# LPC824DIP.net
KiCad netlist of a schematic drawn in EAGLE
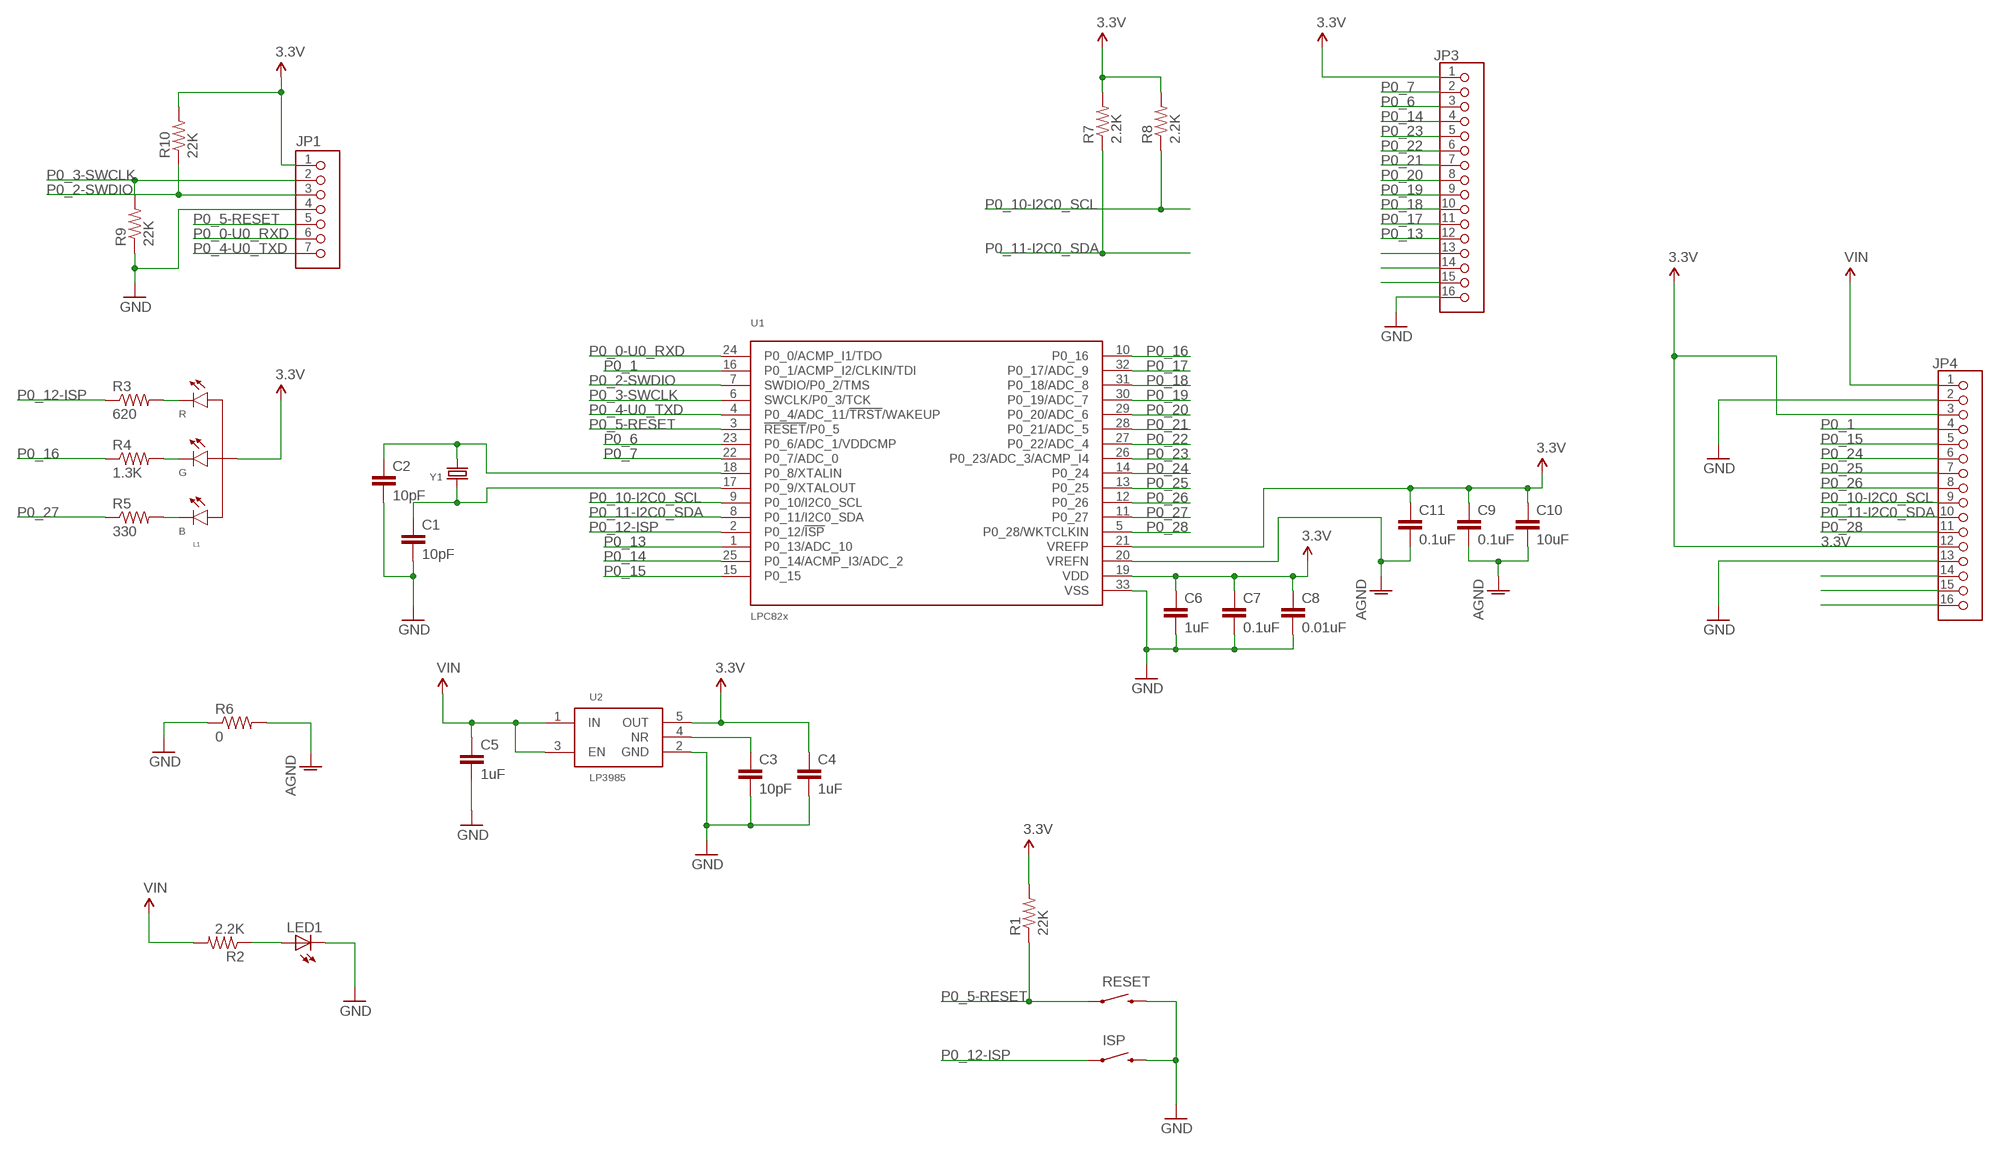
[diagram p0: schematic, sheet 1]

(export (version "E")
  (design (tool "Eeschema 10.0.6"))
  (components
    (comp (ref "C1")
      (value "10pF")
      (footprint "eagle-import:C0402")
      (libsource (lib "eagle-import") (part "C0402"))
    )
    (comp (ref "C2")
      (value "10pF")
      (footprint "eagle-import:C0402")
      (libsource (lib "eagle-import") (part "C0402"))
    )
    (comp (ref "C3")
      (value "10pF")
      (footprint "eagle-import:C0402")
      (libsource (lib "eagle-import") (part "C0402"))
    )
    (comp (ref "C4")
      (value "1uF")
      (footprint "eagle-import:C0402")
      (libsource (lib "eagle-import") (part "C0402"))
    )
    (comp (ref "C5")
      (value "1uF")
      (footprint "eagle-import:C0402")
      (libsource (lib "eagle-import") (part "C0402"))
    )
    (comp (ref "C6")
      (value "1uF")
      (footprint "eagle-import:C0402")
      (libsource (lib "eagle-import") (part "C0402"))
    )
    (comp (ref "C7")
      (value "0.1uF")
      (footprint "eagle-import:C0402")
      (libsource (lib "eagle-import") (part "C0402"))
    )
    (comp (ref "C8")
      (value "0.01uF")
      (footprint "eagle-import:C0402")
      (libsource (lib "eagle-import") (part "C0402"))
    )
    (comp (ref "C9")
      (value "0.1uF")
      (footprint "eagle-import:C0402")
      (libsource (lib "eagle-import") (part "C0402"))
    )
    (comp (ref "C10")
      (value "10uF")
      (footprint "eagle-import:C0402")
      (libsource (lib "eagle-import") (part "C0402"))
    )
    (comp (ref "C11")
      (value "0.1uF")
      (footprint "eagle-import:C0402")
      (libsource (lib "eagle-import") (part "C0402"))
    )
    (comp (ref "ISP")
      (value "KMR221GLFS")
      (footprint "eagle-import:TACTILE_SWITCH_SMD-3")
      (libsource (lib "eagle-import") (part "KMR221GLFS"))
    )
    (comp (ref "JP1")
      (value "HEADER_1X7_JST-SH_VERTICAL")
      (footprint "eagle-import:JST-SH_HEADER_VERTICAL_7")
      (libsource (lib "eagle-import") (part "HEADER_1X7_JST-SH_VERTICAL"))
    )
    (comp (ref "JP3")
      (value "HEADER_1X16")
      (footprint "eagle-import:HEADER_100MIL_1X16")
      (libsource (lib "eagle-import") (part "HEADER_1X16"))
    )
    (comp (ref "JP4")
      (value "HEADER_1X16")
      (footprint "eagle-import:HEADER_100MIL_1X16")
      (libsource (lib "eagle-import") (part "HEADER_1X16"))
    )
    (comp (ref "L1")
      (value "LED_RGB_CA-CLVBA-FKA")
      (footprint "eagle-import:P-LCC4-0")
      (libsource (lib "eagle-import") (part "LED_RGB_CA-CLVBA-FKA"))
    )
    (comp (ref "LED1")
      (value "LEDCHIPLED_0603")
      (footprint "eagle-import:CHIPLED_0603")
      (libsource (lib "eagle-import") (part "LEDCHIPLED_0603"))
    )
    (comp (ref "R1")
      (value "22K")
      (footprint "eagle-import:R0402")
      (libsource (lib "eagle-import") (part "R0402"))
    )
    (comp (ref "R2")
      (value "2.2K")
      (footprint "eagle-import:R0402")
      (libsource (lib "eagle-import") (part "R0402"))
    )
    (comp (ref "R3")
      (value "620")
      (footprint "eagle-import:R0402")
      (libsource (lib "eagle-import") (part "R0402"))
    )
    (comp (ref "R4")
      (value "1.3K")
      (footprint "eagle-import:R0402")
      (libsource (lib "eagle-import") (part "R0402"))
    )
    (comp (ref "R5")
      (value "330")
      (footprint "eagle-import:R0402")
      (libsource (lib "eagle-import") (part "R0402"))
    )
    (comp (ref "R6")
      (value "0")
      (footprint "eagle-import:R0402")
      (libsource (lib "eagle-import") (part "R0402"))
    )
    (comp (ref "R7")
      (value "2.2K")
      (footprint "eagle-import:R0402")
      (libsource (lib "eagle-import") (part "R0402"))
    )
    (comp (ref "R8")
      (value "2.2K")
      (footprint "eagle-import:R0402")
      (libsource (lib "eagle-import") (part "R0402"))
    )
    (comp (ref "R9")
      (value "22K")
      (footprint "eagle-import:R0402")
      (libsource (lib "eagle-import") (part "R0402"))
    )
    (comp (ref "R10")
      (value "22K")
      (footprint "eagle-import:R0402")
      (libsource (lib "eagle-import") (part "R0402"))
    )
    (comp (ref "RESET")
      (value "KMR221GLFS")
      (footprint "eagle-import:TACTILE_SWITCH_SMD-3")
      (libsource (lib "eagle-import") (part "KMR221GLFS"))
    )
    (comp (ref "U1")
      (value "LPC82XMX01JHI33")
      (footprint "eagle-import:QFN33")
      (libsource (lib "eagle-import") (part "LPC82XMX01JHI33"))
    )
    (comp (ref "U2")
      (value "LP3985DBV")
      (footprint "eagle-import:SOT23")
      (libsource (lib "eagle-import") (part "LP3985DBV"))
    )
    (comp (ref "Y1")
      (value "CRYSTAL_3.2X2.5_4PAD")
      (footprint "eagle-import:CRYSTAL_SMD_3.2X2.5_4PAD")
      (libsource (lib "eagle-import") (part "CRYSTAL_3.2X2.5_4PAD"))
    )
  )
  (nets
    (net (code "1") (name "/P0_0-U0_RXD") (class "Default")
      (node (ref "JP1") (pin "6") (pinfunction "6_6") (pintype "passive"))
      (node (ref "JP3") (pin "14") (pinfunction "14_14") (pintype "passive"))
      (node (ref "U1") (pin "24") (pinfunction "P0_0/ACMP_I1/TDO_24") (pintype "bidirectional"))
    )
    (net (code "2") (name "/P0_1") (class "Default")
      (node (ref "JP4") (pin "4") (pinfunction "4_4") (pintype "passive"))
      (node (ref "U1") (pin "16") (pinfunction "P0_1/ACMP_I2/CLKIN/TDI_16") (pintype "bidirectional"))
    )
    (net (code "3") (name "/P0_2-SWDIO") (class "Default")
      (node (ref "JP1") (pin "3") (pinfunction "3_3") (pintype "passive"))
      (node (ref "R10") (pin "1") (pinfunction "1_1") (pintype "passive"))
      (node (ref "U1") (pin "7") (pinfunction "SWDIO/P0_2/TMS_7") (pintype "bidirectional"))
    )
    (net (code "4") (name "/P0_3-SWCLK") (class "Default")
      (node (ref "JP1") (pin "2") (pinfunction "2_2") (pintype "passive"))
      (node (ref "R9") (pin "2") (pinfunction "2_2") (pintype "passive"))
      (node (ref "U1") (pin "6") (pinfunction "SWCLK/P0_3/TCK_6") (pintype "bidirectional"))
    )
    (net (code "5") (name "/P0_4-U0_TXD") (class "Default")
      (node (ref "JP1") (pin "7") (pinfunction "7_7") (pintype "passive"))
      (node (ref "JP3") (pin "13") (pinfunction "13_13") (pintype "passive"))
      (node (ref "U1") (pin "4") (pinfunction "P0_4/ADC_11/~{TRST}/WAKEUP_4") (pintype "bidirectional"))
    )
    (net (code "6") (name "/P0_5-RESET") (class "Default")
      (node (ref "JP1") (pin "5") (pinfunction "5_5") (pintype "passive"))
      (node (ref "JP4") (pin "14") (pinfunction "14_14") (pintype "passive"))
      (node (ref "R1") (pin "1") (pinfunction "1_1") (pintype "passive"))
      (node (ref "RESET") (pin "1") (pinfunction "1_1") (pintype "passive"))
      (node (ref "RESET") (pin "2") (pinfunction "1_2") (pintype "passive"))
      (node (ref "U1") (pin "3") (pinfunction "~{RESET}/P0_5_3") (pintype "bidirectional"))
    )
    (net (code "7") (name "/P0_6") (class "Default")
      (node (ref "JP3") (pin "3") (pinfunction "3_3") (pintype "passive"))
      (node (ref "U1") (pin "23") (pinfunction "P0_6/ADC_1/VDDCMP_23") (pintype "bidirectional"))
    )
    (net (code "8") (name "/P0_7") (class "Default")
      (node (ref "JP3") (pin "2") (pinfunction "2_2") (pintype "passive"))
      (node (ref "U1") (pin "22") (pinfunction "P0_7/ADC_0_22") (pintype "bidirectional"))
    )
    (net (code "9") (name "/P0_10-I2C0_SCL") (class "Default")
      (node (ref "JP4") (pin "9") (pinfunction "9_9") (pintype "passive"))
      (node (ref "R8") (pin "1") (pinfunction "1_1") (pintype "passive"))
      (node (ref "U1") (pin "9") (pinfunction "P0_10/I2C0_SCL_9") (pintype "bidirectional"))
    )
    (net (code "10") (name "/P0_11-I2C0_SDA") (class "Default")
      (node (ref "JP4") (pin "10") (pinfunction "10_10") (pintype "passive"))
      (node (ref "R7") (pin "1") (pinfunction "1_1") (pintype "passive"))
      (node (ref "U1") (pin "8") (pinfunction "P0_11/I2C0_SDA_8") (pintype "bidirectional"))
    )
    (net (code "11") (name "/P0_12-ISP") (class "Default")
      (node (ref "ISP") (pin "1") (pinfunction "1_1") (pintype "passive"))
      (node (ref "ISP") (pin "2") (pinfunction "1_2") (pintype "passive"))
      (node (ref "JP3") (pin "15") (pinfunction "15_15") (pintype "passive"))
      (node (ref "R3") (pin "1") (pinfunction "1_1") (pintype "passive"))
      (node (ref "U1") (pin "2") (pinfunction "P0_12/~{ISP}_2") (pintype "bidirectional"))
    )
    (net (code "12") (name "/P0_13") (class "Default")
      (node (ref "JP3") (pin "12") (pinfunction "12_12") (pintype "passive"))
      (node (ref "U1") (pin "1") (pinfunction "P0_13/ADC_10_1") (pintype "bidirectional"))
    )
    (net (code "13") (name "/P0_14") (class "Default")
      (node (ref "JP3") (pin "4") (pinfunction "4_4") (pintype "passive"))
      (node (ref "U1") (pin "25") (pinfunction "P0_14/ACMP_I3/ADC_2_25") (pintype "bidirectional"))
    )
    (net (code "14") (name "/P0_15") (class "Default")
      (node (ref "JP4") (pin "5") (pinfunction "5_5") (pintype "passive"))
      (node (ref "U1") (pin "15") (pinfunction "P0_15_15") (pintype "bidirectional"))
    )
    (net (code "15") (name "/P0_16") (class "Default")
      (node (ref "JP4") (pin "16") (pinfunction "16_16") (pintype "passive"))
      (node (ref "R4") (pin "1") (pinfunction "1_1") (pintype "passive"))
      (node (ref "U1") (pin "10") (pinfunction "P0_16_10") (pintype "bidirectional"))
    )
    (net (code "16") (name "/P0_17") (class "Default")
      (node (ref "JP3") (pin "11") (pinfunction "11_11") (pintype "passive"))
      (node (ref "U1") (pin "32") (pinfunction "P0_17/ADC_9_32") (pintype "bidirectional"))
    )
    (net (code "17") (name "/P0_18") (class "Default")
      (node (ref "JP3") (pin "10") (pinfunction "10_10") (pintype "passive"))
      (node (ref "U1") (pin "31") (pinfunction "P0_18/ADC_8_31") (pintype "bidirectional"))
    )
    (net (code "18") (name "/P0_19") (class "Default")
      (node (ref "JP3") (pin "9") (pinfunction "9_9") (pintype "passive"))
      (node (ref "U1") (pin "30") (pinfunction "P0_19/ADC_7_30") (pintype "bidirectional"))
    )
    (net (code "19") (name "/P0_20") (class "Default")
      (node (ref "JP3") (pin "8") (pinfunction "8_8") (pintype "passive"))
      (node (ref "U1") (pin "29") (pinfunction "P0_20/ADC_6_29") (pintype "bidirectional"))
    )
    (net (code "20") (name "/P0_21") (class "Default")
      (node (ref "JP3") (pin "7") (pinfunction "7_7") (pintype "passive"))
      (node (ref "U1") (pin "28") (pinfunction "P0_21/ADC_5_28") (pintype "bidirectional"))
    )
    (net (code "21") (name "/P0_22") (class "Default")
      (node (ref "JP3") (pin "6") (pinfunction "6_6") (pintype "passive"))
      (node (ref "U1") (pin "27") (pinfunction "P0_22/ADC_4_27") (pintype "bidirectional"))
    )
    (net (code "22") (name "/P0_23") (class "Default")
      (node (ref "JP3") (pin "5") (pinfunction "5_5") (pintype "passive"))
      (node (ref "U1") (pin "26") (pinfunction "P0_23/ADC_3/ACMP_I4_26") (pintype "bidirectional"))
    )
    (net (code "23") (name "/P0_24") (class "Default")
      (node (ref "JP4") (pin "6") (pinfunction "6_6") (pintype "passive"))
      (node (ref "U1") (pin "14") (pinfunction "P0_24_14") (pintype "bidirectional"))
    )
    (net (code "24") (name "/P0_25") (class "Default")
      (node (ref "JP4") (pin "7") (pinfunction "7_7") (pintype "passive"))
      (node (ref "U1") (pin "13") (pinfunction "P0_25_13") (pintype "bidirectional"))
    )
    (net (code "25") (name "/P0_26") (class "Default")
      (node (ref "JP4") (pin "8") (pinfunction "8_8") (pintype "passive"))
      (node (ref "U1") (pin "12") (pinfunction "P0_26_12") (pintype "bidirectional"))
    )
    (net (code "26") (name "/P0_27") (class "Default")
      (node (ref "JP4") (pin "15") (pinfunction "15_15") (pintype "passive"))
      (node (ref "R5") (pin "1") (pinfunction "1_1") (pintype "passive"))
      (node (ref "U1") (pin "11") (pinfunction "P0_27_11") (pintype "bidirectional"))
    )
    (net (code "27") (name "/P0_28") (class "Default")
      (node (ref "JP4") (pin "11") (pinfunction "11_11") (pintype "passive"))
      (node (ref "U1") (pin "5") (pinfunction "P0_28/WKTCLKIN_5") (pintype "bidirectional"))
    )
    (net (code "28") (name "3.3V") (class "Default")
      (node (ref "C10") (pin "1") (pinfunction "1_1") (pintype "passive"))
      (node (ref "C11") (pin "1") (pinfunction "1_1") (pintype "passive"))
      (node (ref "C4") (pin "1") (pinfunction "1_1") (pintype "passive"))
      (node (ref "C6") (pin "1") (pinfunction "1_1") (pintype "passive"))
      (node (ref "C7") (pin "1") (pinfunction "1_1") (pintype "passive"))
      (node (ref "C8") (pin "1") (pinfunction "1_1") (pintype "passive"))
      (node (ref "C9") (pin "1") (pinfunction "1_1") (pintype "passive"))
      (node (ref "JP1") (pin "1") (pinfunction "1_1") (pintype "passive"))
      (node (ref "JP3") (pin "1") (pinfunction "1_1") (pintype "passive"))
      (node (ref "JP4") (pin "12") (pinfunction "12_12") (pintype "passive"))
      (node (ref "JP4") (pin "3") (pinfunction "3_3") (pintype "passive"))
      (node (ref "L1") (pin "2") (pinfunction "A_2") (pintype "bidirectional"))
      (node (ref "R1") (pin "2") (pinfunction "2_2") (pintype "passive"))
      (node (ref "R10") (pin "2") (pinfunction "2_2") (pintype "passive"))
      (node (ref "R7") (pin "2") (pinfunction "2_2") (pintype "passive"))
      (node (ref "R8") (pin "2") (pinfunction "2_2") (pintype "passive"))
      (node (ref "U1") (pin "19") (pinfunction "VDD_19") (pintype "power_in"))
      (node (ref "U1") (pin "21") (pinfunction "VREFP_21") (pintype "power_in"))
      (node (ref "U2") (pin "5") (pinfunction "OUT_5") (pintype "power_in"))
    )
    (net (code "29") (name "AGND") (class "Default")
      (node (ref "C10") (pin "2") (pinfunction "2_2") (pintype "passive"))
      (node (ref "C11") (pin "2") (pinfunction "2_2") (pintype "passive"))
      (node (ref "C9") (pin "2") (pinfunction "2_2") (pintype "passive"))
      (node (ref "R6") (pin "2") (pinfunction "2_2") (pintype "passive"))
      (node (ref "U1") (pin "20") (pinfunction "VREFN_20") (pintype "power_in"))
    )
    (net (code "30") (name "GND") (class "Default")
      (node (ref "C1") (pin "2") (pinfunction "2_2") (pintype "passive"))
      (node (ref "C2") (pin "2") (pinfunction "2_2") (pintype "passive"))
      (node (ref "C3") (pin "2") (pinfunction "2_2") (pintype "passive"))
      (node (ref "C4") (pin "2") (pinfunction "2_2") (pintype "passive"))
      (node (ref "C5") (pin "2") (pinfunction "2_2") (pintype "passive"))
      (node (ref "C6") (pin "2") (pinfunction "2_2") (pintype "passive"))
      (node (ref "C7") (pin "2") (pinfunction "2_2") (pintype "passive"))
      (node (ref "C8") (pin "2") (pinfunction "2_2") (pintype "passive"))
      (node (ref "ISP") (pin "3") (pinfunction "2_3") (pintype "passive"))
      (node (ref "ISP") (pin "4") (pinfunction "2_4") (pintype "passive"))
      (node (ref "JP1") (pin "4") (pinfunction "4_4") (pintype "passive"))
      (node (ref "JP3") (pin "16") (pinfunction "16_16") (pintype "passive"))
      (node (ref "JP4") (pin "13") (pinfunction "13_13") (pintype "passive"))
      (node (ref "JP4") (pin "2") (pinfunction "2_2") (pintype "passive"))
      (node (ref "LED1") (pin "C") (pinfunction "C_C") (pintype "passive"))
      (node (ref "R6") (pin "1") (pinfunction "1_1") (pintype "passive"))
      (node (ref "R9") (pin "1") (pinfunction "1_1") (pintype "passive"))
      (node (ref "RESET") (pin "3") (pinfunction "2_3") (pintype "passive"))
      (node (ref "RESET") (pin "4") (pinfunction "2_4") (pintype "passive"))
      (node (ref "U1") (pin "33") (pinfunction "VSS_33") (pintype "power_in"))
      (node (ref "U2") (pin "2") (pinfunction "GND_2") (pintype "power_in"))
    )
    (net (code "31") (name "Net-(L1-BK)") (class "Default")
      (node (ref "L1") (pin "3") (pinfunction "BK_3") (pintype "bidirectional"))
      (node (ref "R5") (pin "2") (pinfunction "2_2") (pintype "passive"))
    )
    (net (code "32") (name "Net-(L1-GK)") (class "Default")
      (node (ref "L1") (pin "4") (pinfunction "GK_4") (pintype "bidirectional"))
      (node (ref "R4") (pin "2") (pinfunction "2_2") (pintype "passive"))
    )
    (net (code "33") (name "Net-(L1-RK)") (class "Default")
      (node (ref "L1") (pin "1") (pinfunction "RK_1") (pintype "bidirectional"))
      (node (ref "R3") (pin "2") (pinfunction "2_2") (pintype "passive"))
    )
    (net (code "34") (name "Net-(LED1-PadA)") (class "Default")
      (node (ref "LED1") (pin "A") (pinfunction "A_A") (pintype "passive"))
      (node (ref "R2") (pin "1") (pinfunction "1_1") (pintype "passive"))
    )
    (net (code "35") (name "Net-(U1-P0_8{slash}XTALIN)") (class "Default")
      (node (ref "C2") (pin "1") (pinfunction "1_1") (pintype "passive"))
      (node (ref "U1") (pin "18") (pinfunction "P0_8/XTALIN_18") (pintype "bidirectional"))
      (node (ref "Y1") (pin "3") (pinfunction "P$2_3") (pintype "bidirectional"))
    )
    (net (code "36") (name "Net-(U1-P0_9{slash}XTALOUT)") (class "Default")
      (node (ref "C1") (pin "1") (pinfunction "1_1") (pintype "passive"))
      (node (ref "U1") (pin "17") (pinfunction "P0_9/XTALOUT_17") (pintype "bidirectional"))
      (node (ref "Y1") (pin "1") (pinfunction "P$1_1") (pintype "bidirectional"))
    )
    (net (code "37") (name "Net-(U2-NR)") (class "Default")
      (node (ref "C3") (pin "1") (pinfunction "1_1") (pintype "passive"))
      (node (ref "U2") (pin "4") (pinfunction "NR_4") (pintype "output"))
    )
    (net (code "38") (name "VIN") (class "Default")
      (node (ref "C5") (pin "1") (pinfunction "1_1") (pintype "passive"))
      (node (ref "JP4") (pin "1") (pinfunction "1_1") (pintype "passive"))
      (node (ref "R2") (pin "2") (pinfunction "2_2") (pintype "passive"))
      (node (ref "U2") (pin "1") (pinfunction "IN_1") (pintype "power_in"))
      (node (ref "U2") (pin "3") (pinfunction "EN_3") (pintype "input"))
    )
  )
)
